# ProProject_3rd-Chebyshev-BPF-3_5-54M.net
KiCad netlist of a schematic drawn in EasyEDA Pro
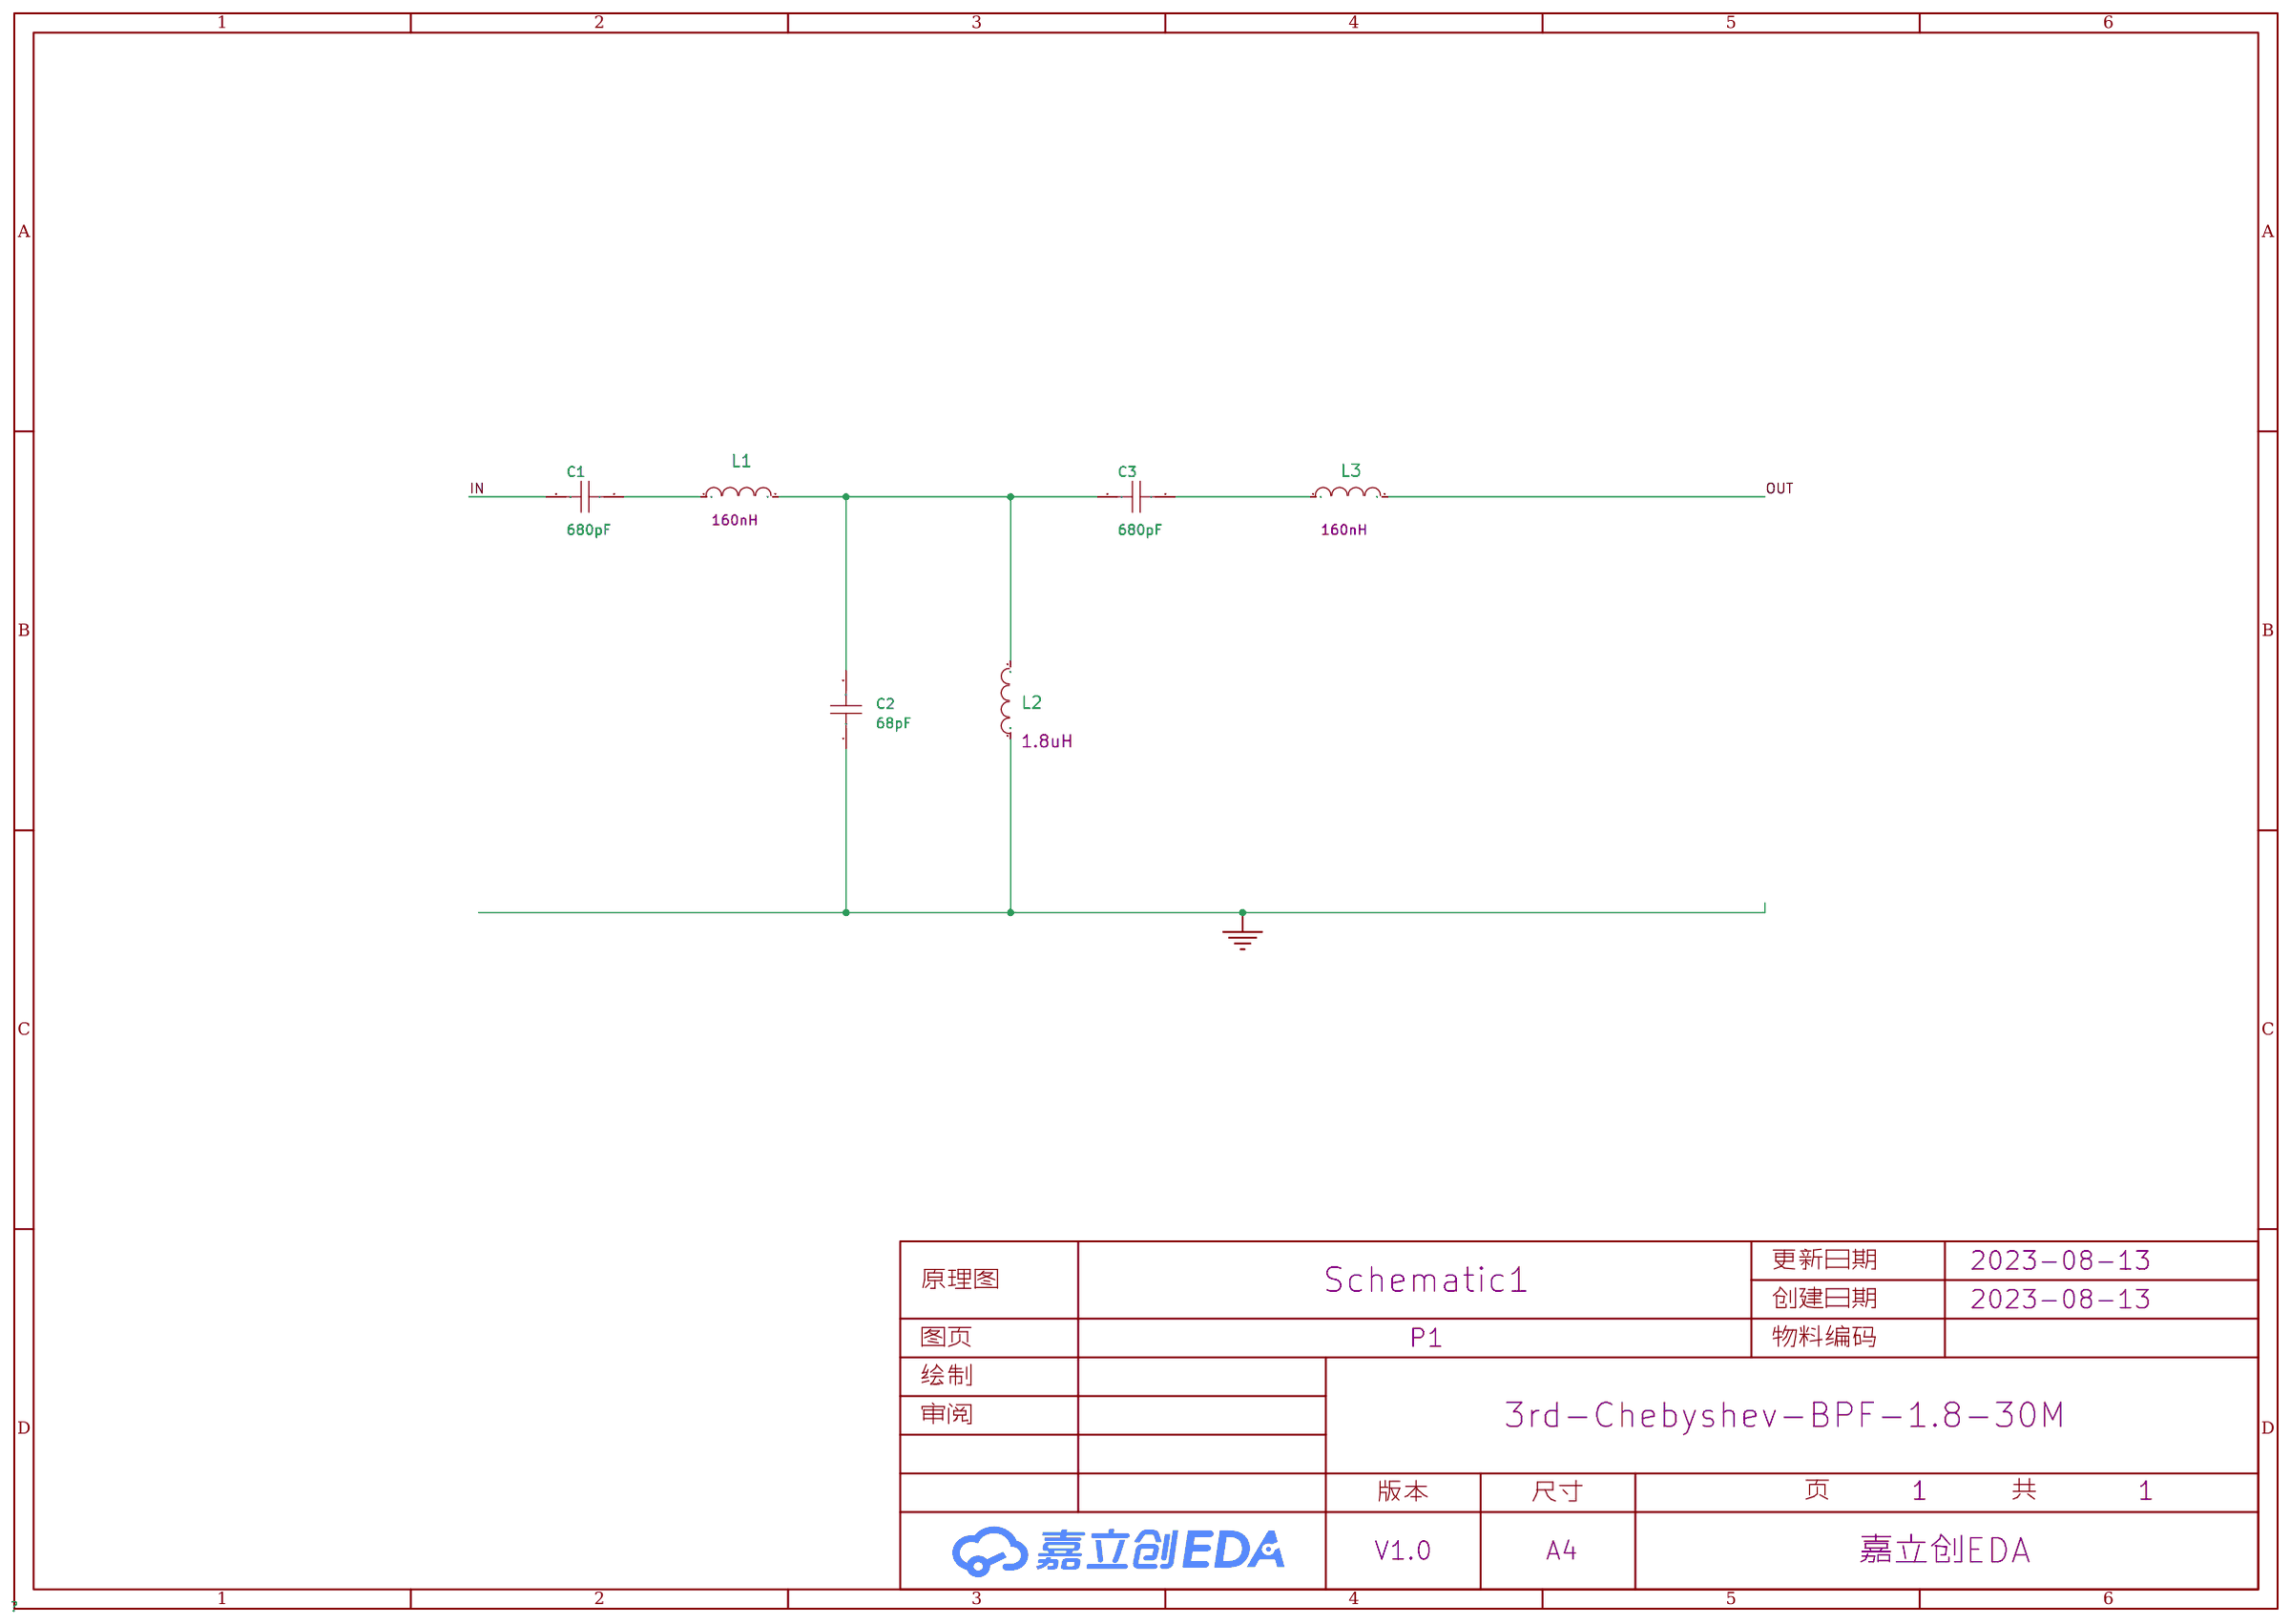
[diagram p0: schematic sheet]

(export (version "E")
  (design (tool "Eeschema 10.0.6"))
  (components
    (comp (ref "C1")
      (value "680pF")
      (footprint "easyedapro:CAP-TH_L8.0-W4.0-P5.00-D1.2")
      (description "容值:820pF;精度:±10%;额定电压:2kV;温度系数:Y5P;")
      (fields (field (name "Manufacturer Part") "CT81-M7Y5P1B821KSE") (field (name "Manufacturer") "FH(风华)"))
      (libsource (lib "easyedapro") (part "CT81-M7Y5P1B821KSE"))
    )
    (comp (ref "C2")
      (value "68pF")
      (footprint "easyedapro:CAP-TH_L8.0-W4.0-P5.00-D1.2")
      (description "容值:820pF;精度:±10%;额定电压:2kV;温度系数:Y5P;")
      (fields (field (name "Manufacturer Part") "CT81-M7Y5P1B821KSE") (field (name "Manufacturer") "FH(风华)"))
      (libsource (lib "easyedapro") (part "CT81-M7Y5P1B821KSE"))
    )
    (comp (ref "C3")
      (value "680pF")
      (footprint "easyedapro:CAP-TH_L8.0-W4.0-P5.00-D1.2")
      (description "容值:820pF;精度:±10%;额定电压:2kV;温度系数:Y5P;")
      (fields (field (name "Manufacturer Part") "CT81-M7Y5P1B821KSE") (field (name "Manufacturer") "FH(风华)"))
      (libsource (lib "easyedapro") (part "CT81-M7Y5P1B821KSE"))
    )
    (comp (ref "L1")
      (value "~")
      (fields (field (name "Inductance") "160nH"))
      (libsource (lib "easyedapro") (part "直插电感8mm"))
    )
    (comp (ref "L2")
      (value "~")
      (fields (field (name "Inductance") "1.8uH"))
      (libsource (lib "easyedapro") (part "直插电感8mm"))
    )
    (comp (ref "L3")
      (value "~")
      (fields (field (name "Inductance") "160nH"))
      (libsource (lib "easyedapro") (part "直插电感8mm"))
    )
  )
  (nets
    (net (code "1") (name "/IN") (class "Default")
      (node (ref "C1") (pin "2") (pinfunction "2_2") (pintype "input"))
    )
    (net (code "2") (name "/OUT") (class "Default")
      (node (ref "L3") (pin "2") (pinfunction "2_2") (pintype "input"))
    )
    (net (code "3") (name "GND") (class "Default")
      (node (ref "C2") (pin "1") (pinfunction "1_1") (pintype "input"))
      (node (ref "L2") (pin "1") (pinfunction "1_1") (pintype "input"))
    )
    (net (code "4") (name "Net-(C1-Pad1)") (class "Default")
      (node (ref "C1") (pin "1") (pinfunction "1_1") (pintype "input"))
      (node (ref "L1") (pin "1") (pinfunction "1_1") (pintype "input"))
    )
    (net (code "5") (name "Net-(C2-Pad2)") (class "Default")
      (node (ref "C2") (pin "2") (pinfunction "2_2") (pintype "input"))
      (node (ref "C3") (pin "2") (pinfunction "2_2") (pintype "input"))
      (node (ref "L1") (pin "2") (pinfunction "2_2") (pintype "input"))
      (node (ref "L2") (pin "2") (pinfunction "2_2") (pintype "input"))
    )
    (net (code "6") (name "Net-(C3-Pad1)") (class "Default")
      (node (ref "C3") (pin "1") (pinfunction "1_1") (pintype "input"))
      (node (ref "L3") (pin "1") (pinfunction "1_1") (pintype "input"))
    )
  )
)
